# G35InjectorV1.net
KiCad netlist of a schematic drawn in EAGLE
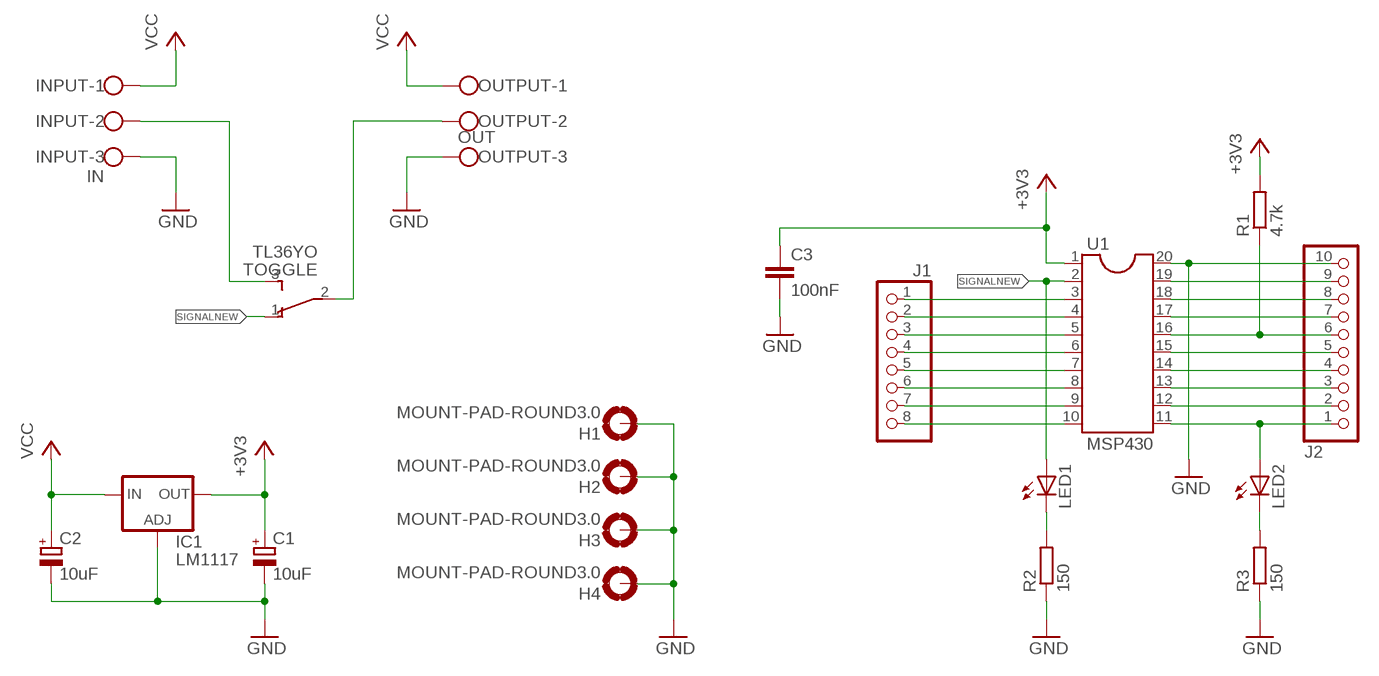
[diagram p0: schematic, sheet 1]

(export (version "E")
  (design (tool "Eeschema 10.0.6"))
  (components
    (comp (ref "C1")
      (value "10uF")
      (footprint "eagle-import:E5-10,5")
      (libsource (lib "eagle-import") (part "CPOL-EUE5-10.5"))
    )
    (comp (ref "C2")
      (value "10uF")
      (footprint "eagle-import:E5-10,5")
      (libsource (lib "eagle-import") (part "CPOL-EUE5-10.5"))
    )
    (comp (ref "C3")
      (value "100nF")
      (footprint "eagle-import:C0805")
      (libsource (lib "eagle-import") (part "C-EUC0805"))
    )
    (comp (ref "H1")
      (value "MOUNT-PAD-ROUND3.0")
      (footprint "eagle-import:3,0-PAD")
      (libsource (lib "eagle-import") (part "MOUNT-PAD-ROUND3.0"))
    )
    (comp (ref "H2")
      (value "MOUNT-PAD-ROUND3.0")
      (footprint "eagle-import:3,0-PAD")
      (libsource (lib "eagle-import") (part "MOUNT-PAD-ROUND3.0"))
    )
    (comp (ref "H3")
      (value "MOUNT-PAD-ROUND3.0")
      (footprint "eagle-import:3,0-PAD")
      (libsource (lib "eagle-import") (part "MOUNT-PAD-ROUND3.0"))
    )
    (comp (ref "H4")
      (value "MOUNT-PAD-ROUND3.0")
      (footprint "eagle-import:3,0-PAD")
      (libsource (lib "eagle-import") (part "MOUNT-PAD-ROUND3.0"))
    )
    (comp (ref "IC1")
      (value "LM1117")
      (footprint "eagle-import:317TS")
      (libsource (lib "eagle-import") (part "LM317TS"))
    )
    (comp (ref "INPUT")
      (value "IN")
      (footprint "eagle-import:W237-103")
      (fields (field (name "MPN") "237-103"))
      (libsource (lib "eagle-import") (part "W237-103"))
    )
    (comp (ref "J1")
      (value "PINHD-1X8")
      (footprint "eagle-import:1X08")
      (libsource (lib "eagle-import") (part "PINHD-1X8"))
    )
    (comp (ref "J2")
      (value "PINHD-1X10")
      (footprint "eagle-import:1X10")
      (libsource (lib "eagle-import") (part "PINHD-1X10"))
    )
    (comp (ref "LED1")
      (value "LED5MM")
      (footprint "eagle-import:LED5MM")
      (libsource (lib "eagle-import") (part "LED5MM"))
    )
    (comp (ref "LED2")
      (value "LED5MM")
      (footprint "eagle-import:LED5MM")
      (libsource (lib "eagle-import") (part "LED5MM"))
    )
    (comp (ref "OUTPUT")
      (value "OUT")
      (footprint "eagle-import:W237-103")
      (fields (field (name "MPN") "237-103"))
      (libsource (lib "eagle-import") (part "W237-103"))
    )
    (comp (ref "R1")
      (value "4.7k")
      (footprint "eagle-import:R0805")
      (libsource (lib "eagle-import") (part "R-EU_R0805"))
    )
    (comp (ref "R2")
      (value "150")
      (footprint "eagle-import:R0805")
      (libsource (lib "eagle-import") (part "R-EU_R0805"))
    )
    (comp (ref "R3")
      (value "150")
      (footprint "eagle-import:R0805")
      (libsource (lib "eagle-import") (part "R-EU_R0805"))
    )
    (comp (ref "TOGGLE")
      (value "TL36YO")
      (footprint "eagle-import:TL3XYO")
      (libsource (lib "eagle-import") (part "TL36YO"))
    )
    (comp (ref "U1")
      (value "MSP430")
      (footprint "eagle-import:SOCKET-20")
      (libsource (lib "eagle-import") (part "DIL20S"))
    )
  )
  (nets
    (net (code "1") (name "+3V3") (class "Default")
      (node (ref "C1") (pin "+") (pinfunction "+_+") (pintype "passive"))
      (node (ref "C3") (pin "1") (pinfunction "1_1") (pintype "passive"))
      (node (ref "IC1") (pin "2") (pinfunction "OUT_2") (pintype "passive"))
      (node (ref "R1") (pin "2") (pinfunction "2_2") (pintype "passive"))
      (node (ref "U1") (pin "1") (pinfunction "1_1") (pintype "passive"))
    )
    (net (code "2") (name "GND") (class "Default")
      (node (ref "C1") (pin "-") (pinfunction "-_-") (pintype "passive"))
      (node (ref "C2") (pin "-") (pinfunction "-_-") (pintype "passive"))
      (node (ref "C3") (pin "2") (pinfunction "2_2") (pintype "passive"))
      (node (ref "H1") (pin "B3,0") (pinfunction "MOUNT_B3,0") (pintype "passive"))
      (node (ref "H2") (pin "B3,0") (pinfunction "MOUNT_B3,0") (pintype "passive"))
      (node (ref "H3") (pin "B3,0") (pinfunction "MOUNT_B3,0") (pintype "passive"))
      (node (ref "H4") (pin "B3,0") (pinfunction "MOUNT_B3,0") (pintype "passive"))
      (node (ref "IC1") (pin "1") (pinfunction "ADJ_1") (pintype "input"))
      (node (ref "INPUT") (pin "3") (pinfunction "KL_3") (pintype "passive"))
      (node (ref "J2") (pin "10") (pinfunction "10_10") (pintype "passive"))
      (node (ref "OUTPUT") (pin "3") (pinfunction "KL_3") (pintype "passive"))
      (node (ref "R2") (pin "1") (pinfunction "1_1") (pintype "passive"))
      (node (ref "R3") (pin "1") (pinfunction "1_1") (pintype "passive"))
      (node (ref "U1") (pin "20") (pinfunction "20_20") (pintype "passive"))
    )
    (net (code "3") (name "Net-(INPUTB-KL)") (class "Default")
      (node (ref "INPUT") (pin "2") (pinfunction "KL_2") (pintype "passive"))
      (node (ref "TOGGLE") (pin "3") (pinfunction "S_3") (pintype "passive"))
    )
    (net (code "4") (name "Net-(J1-Pad1)") (class "Default")
      (node (ref "J1") (pin "1") (pinfunction "1_1") (pintype "passive"))
      (node (ref "U1") (pin "3") (pinfunction "3_3") (pintype "passive"))
    )
    (net (code "5") (name "Net-(J1-Pad2)") (class "Default")
      (node (ref "J1") (pin "2") (pinfunction "2_2") (pintype "passive"))
      (node (ref "U1") (pin "4") (pinfunction "4_4") (pintype "passive"))
    )
    (net (code "6") (name "Net-(J1-Pad3)") (class "Default")
      (node (ref "J1") (pin "3") (pinfunction "3_3") (pintype "passive"))
      (node (ref "U1") (pin "5") (pinfunction "5_5") (pintype "passive"))
    )
    (net (code "7") (name "Net-(J1-Pad4)") (class "Default")
      (node (ref "J1") (pin "4") (pinfunction "4_4") (pintype "passive"))
      (node (ref "U1") (pin "6") (pinfunction "6_6") (pintype "passive"))
    )
    (net (code "8") (name "Net-(J1-Pad5)") (class "Default")
      (node (ref "J1") (pin "5") (pinfunction "5_5") (pintype "passive"))
      (node (ref "U1") (pin "7") (pinfunction "7_7") (pintype "passive"))
    )
    (net (code "9") (name "Net-(J1-Pad6)") (class "Default")
      (node (ref "J1") (pin "6") (pinfunction "6_6") (pintype "passive"))
      (node (ref "U1") (pin "8") (pinfunction "8_8") (pintype "passive"))
    )
    (net (code "10") (name "Net-(J1-Pad7)") (class "Default")
      (node (ref "J1") (pin "7") (pinfunction "7_7") (pintype "passive"))
      (node (ref "U1") (pin "9") (pinfunction "9_9") (pintype "passive"))
    )
    (net (code "11") (name "Net-(J1-Pad8)") (class "Default")
      (node (ref "J1") (pin "8") (pinfunction "8_8") (pintype "passive"))
      (node (ref "U1") (pin "10") (pinfunction "10_10") (pintype "passive"))
    )
    (net (code "12") (name "Net-(J2-Pad1)") (class "Default")
      (node (ref "J2") (pin "1") (pinfunction "1_1") (pintype "passive"))
      (node (ref "LED2") (pin "A") (pinfunction "A_A") (pintype "passive"))
      (node (ref "U1") (pin "11") (pinfunction "11_11") (pintype "passive"))
    )
    (net (code "13") (name "Net-(J2-Pad2)") (class "Default")
      (node (ref "J2") (pin "2") (pinfunction "2_2") (pintype "passive"))
      (node (ref "U1") (pin "12") (pinfunction "12_12") (pintype "passive"))
    )
    (net (code "14") (name "Net-(J2-Pad3)") (class "Default")
      (node (ref "J2") (pin "3") (pinfunction "3_3") (pintype "passive"))
      (node (ref "U1") (pin "13") (pinfunction "13_13") (pintype "passive"))
    )
    (net (code "15") (name "Net-(J2-Pad4)") (class "Default")
      (node (ref "J2") (pin "4") (pinfunction "4_4") (pintype "passive"))
      (node (ref "U1") (pin "14") (pinfunction "14_14") (pintype "passive"))
    )
    (net (code "16") (name "Net-(J2-Pad5)") (class "Default")
      (node (ref "J2") (pin "5") (pinfunction "5_5") (pintype "passive"))
      (node (ref "U1") (pin "15") (pinfunction "15_15") (pintype "passive"))
    )
    (net (code "17") (name "Net-(J2-Pad6)") (class "Default")
      (node (ref "J2") (pin "6") (pinfunction "6_6") (pintype "passive"))
      (node (ref "R1") (pin "1") (pinfunction "1_1") (pintype "passive"))
      (node (ref "U1") (pin "16") (pinfunction "16_16") (pintype "passive"))
    )
    (net (code "18") (name "Net-(J2-Pad7)") (class "Default")
      (node (ref "J2") (pin "7") (pinfunction "7_7") (pintype "passive"))
      (node (ref "U1") (pin "17") (pinfunction "17_17") (pintype "passive"))
    )
    (net (code "19") (name "Net-(J2-Pad8)") (class "Default")
      (node (ref "J2") (pin "8") (pinfunction "8_8") (pintype "passive"))
      (node (ref "U1") (pin "18") (pinfunction "18_18") (pintype "passive"))
    )
    (net (code "20") (name "Net-(J2-Pad9)") (class "Default")
      (node (ref "J2") (pin "9") (pinfunction "9_9") (pintype "passive"))
      (node (ref "U1") (pin "19") (pinfunction "19_19") (pintype "passive"))
    )
    (net (code "21") (name "Net-(LED1-C)") (class "Default")
      (node (ref "LED1") (pin "K") (pinfunction "C_K") (pintype "passive"))
      (node (ref "R2") (pin "2") (pinfunction "2_2") (pintype "passive"))
    )
    (net (code "22") (name "Net-(LED2-C)") (class "Default")
      (node (ref "LED2") (pin "K") (pinfunction "C_K") (pintype "passive"))
      (node (ref "R3") (pin "2") (pinfunction "2_2") (pintype "passive"))
    )
    (net (code "23") (name "Net-(OUTPUTB-KL)") (class "Default")
      (node (ref "OUTPUT") (pin "2") (pinfunction "KL_2") (pintype "passive"))
      (node (ref "TOGGLE") (pin "2") (pinfunction "P_2") (pintype "passive"))
    )
    (net (code "24") (name "SIGNALNEW") (class "Default")
      (node (ref "LED1") (pin "A") (pinfunction "A_A") (pintype "passive"))
      (node (ref "TOGGLE") (pin "1") (pinfunction "O_1") (pintype "passive"))
      (node (ref "U1") (pin "2") (pinfunction "2_2") (pintype "passive"))
    )
    (net (code "25") (name "VCC") (class "Default")
      (node (ref "C2") (pin "+") (pinfunction "+_+") (pintype "passive"))
      (node (ref "IC1") (pin "3") (pinfunction "IN_3") (pintype "input"))
      (node (ref "INPUT") (pin "1") (pinfunction "KL_1") (pintype "passive"))
      (node (ref "OUTPUT") (pin "1") (pinfunction "KL_1") (pintype "passive"))
    )
  )
)
